# Wattuino-Nanite85_v10.net
KiCad netlist of a schematic drawn in EAGLE
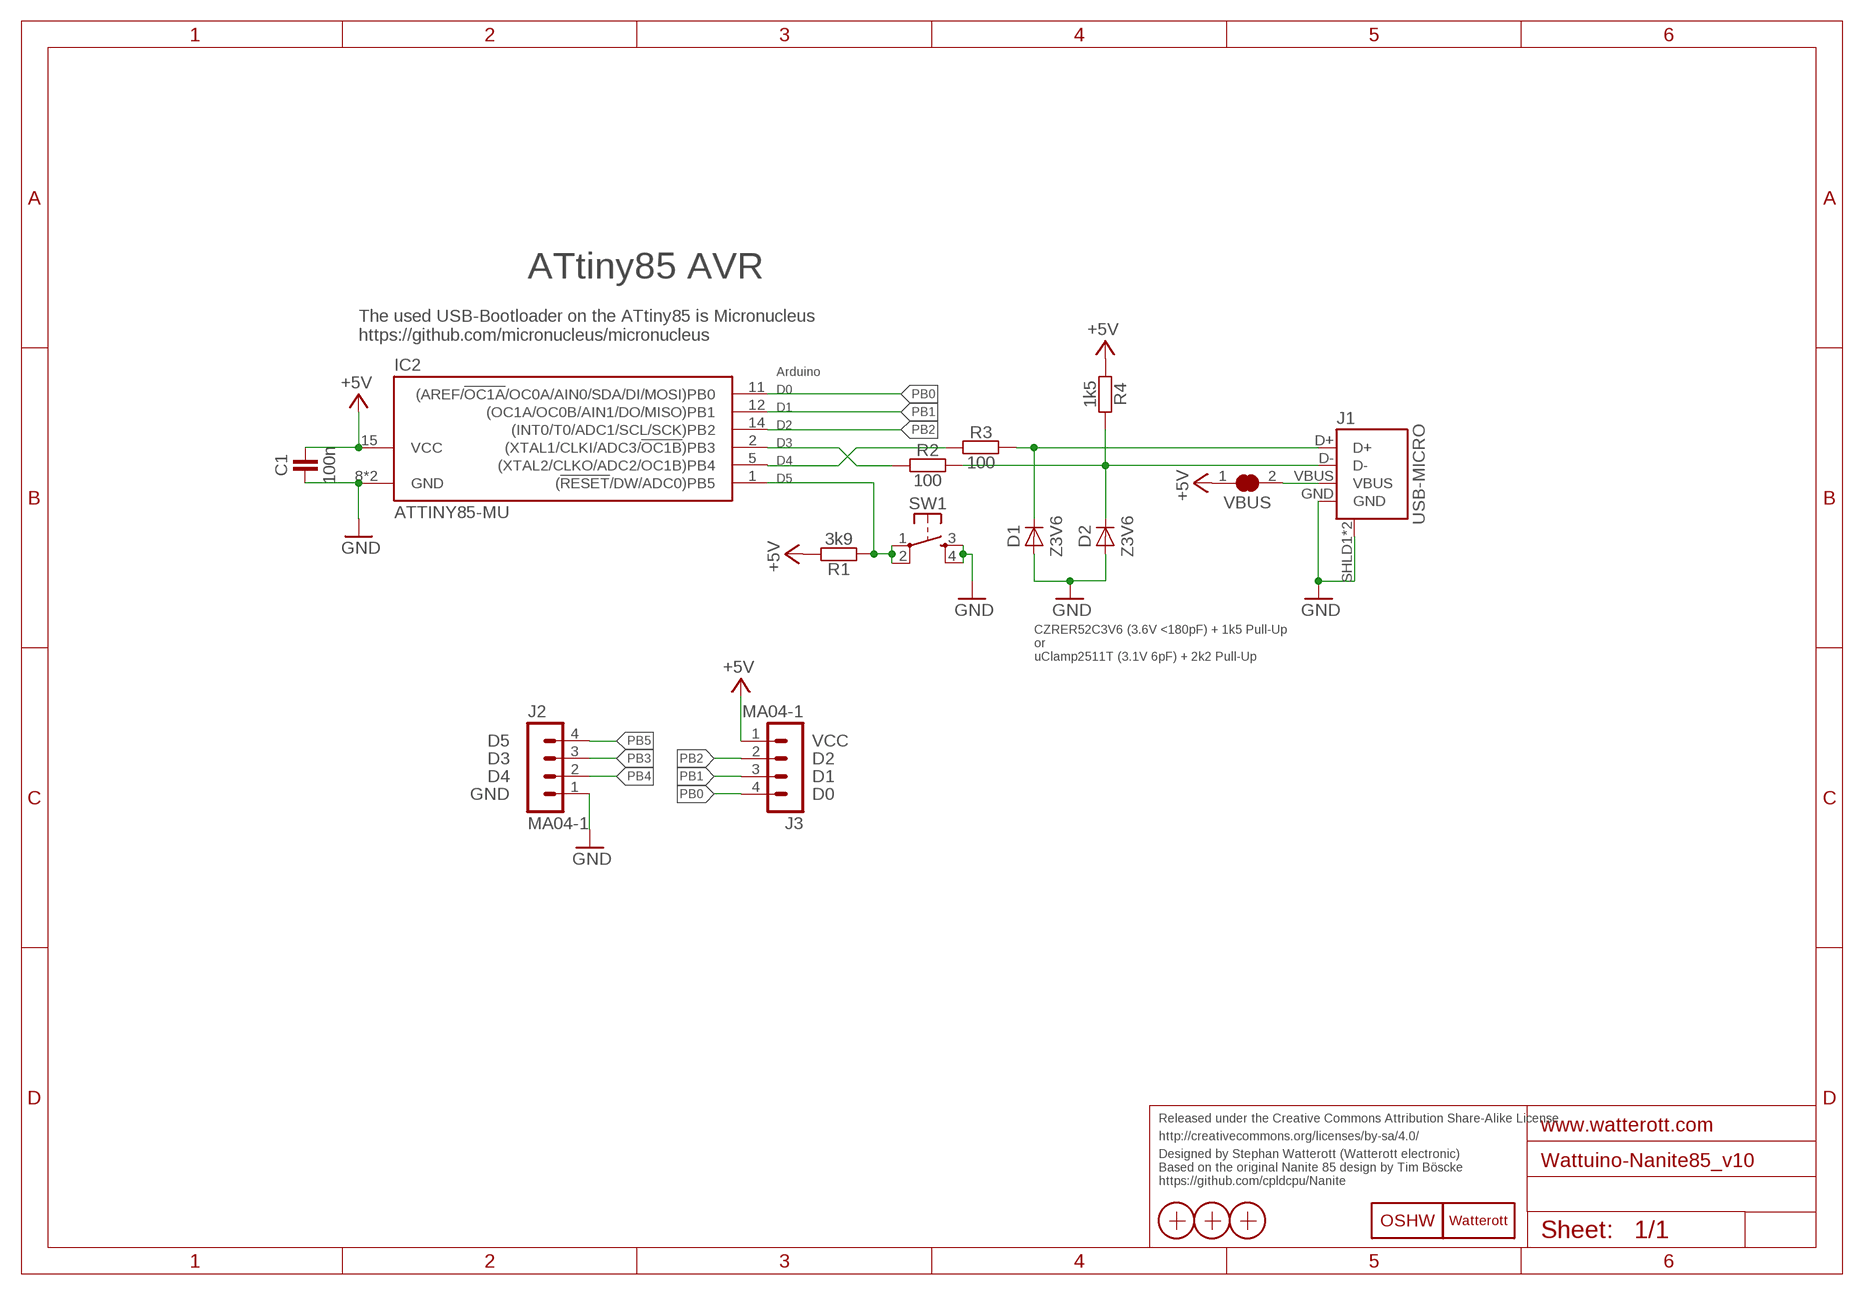
[diagram p0: schematic, sheet 1]

(export (version "E")
  (design (tool "Eeschema 10.0.6"))
  (components
    (comp (ref "C1")
      (value "100n")
      (footprint "eagle-import:C0402")
      (libsource (lib "eagle-import") (part "CAPACITOR-0402"))
    )
    (comp (ref "D1")
      (value "Z3V6")
      (footprint "eagle-import:SOD882")
      (libsource (lib "eagle-import") (part "DIODE-SOD882"))
    )
    (comp (ref "D2")
      (value "Z3V6")
      (footprint "eagle-import:SOD882")
      (libsource (lib "eagle-import") (part "DIODE-SOD882"))
    )
    (comp (ref "IC2")
      (value "ATTINY85-MU")
      (footprint "eagle-import:QFN20-PAD")
      (libsource (lib "eagle-import") (part "ATTINY85-MU"))
    )
    (comp (ref "J1")
      (value "USB-MICRO")
      (footprint "eagle-import:USB-MICRO-10103594")
      (libsource (lib "eagle-import") (part "USB-MICRO"))
    )
    (comp (ref "J2")
      (value "MA04-1")
      (footprint "eagle-import:MA04-1")
      (libsource (lib "eagle-import") (part "MA04-1"))
    )
    (comp (ref "J3")
      (value "MA04-1")
      (footprint "eagle-import:MA04-1")
      (libsource (lib "eagle-import") (part "MA04-1"))
    )
    (comp (ref "LOGO1")
      (value "LOGO-S_PLACE_S")
      (footprint "eagle-import:SPARK_TPLACE_S")
      (libsource (lib "eagle-import") (part "LOGO-S_PLACE_S"))
    )
    (comp (ref "LOGO2")
      (value "OSHW_LOGOX0070")
      (footprint "eagle-import:OSHW_6X70")
      (libsource (lib "eagle-import") (part "OSHW_LOGOX0070"))
    )
    (comp (ref "R1")
      (value "3k9")
      (footprint "eagle-import:C0402")
      (libsource (lib "eagle-import") (part "RESISTOR-0402"))
    )
    (comp (ref "R2")
      (value "100")
      (footprint "eagle-import:C0402")
      (libsource (lib "eagle-import") (part "RESISTOR-0402"))
    )
    (comp (ref "R3")
      (value "100")
      (footprint "eagle-import:C0402")
      (libsource (lib "eagle-import") (part "RESISTOR-0402"))
    )
    (comp (ref "R4")
      (value "1k5")
      (footprint "eagle-import:C0402")
      (libsource (lib "eagle-import") (part "RESISTOR-0402"))
    )
    (comp (ref "SW1")
      (value "SW-TACTILE-PTS840P")
      (footprint "eagle-import:SW_PTS840P")
      (libsource (lib "eagle-import") (part "SW-TACTILE-PTS840P"))
    )
    (comp (ref "VBUS")
      (value "JUMPER2-0603-NC")
      (footprint "eagle-import:JUMPER2-0603_NC")
      (libsource (lib "eagle-import") (part "JUMPER2-0603-NC"))
    )
    (comp (ref "X1")
      (value "PASSER-07")
      (footprint "eagle-import:PASSER_07MM")
      (libsource (lib "eagle-import") (part "PASSER-07"))
    )
    (comp (ref "X2")
      (value "PASSER-07")
      (footprint "eagle-import:PASSER_07MM")
      (libsource (lib "eagle-import") (part "PASSER-07"))
    )
    (comp (ref "X3")
      (value "PASSER-07")
      (footprint "eagle-import:PASSER_07MM")
      (libsource (lib "eagle-import") (part "PASSER-07"))
    )
  )
  (nets
    (net (code "1") (name "+5V") (class "Default")
      (node (ref "C1") (pin "2") (pinfunction "2_2") (pintype "passive"))
      (node (ref "IC2") (pin "15") (pinfunction "VCC_15") (pintype "power_in"))
      (node (ref "J3") (pin "1") (pinfunction "1_1") (pintype "passive"))
      (node (ref "R1") (pin "2") (pinfunction "2_2") (pintype "passive"))
      (node (ref "R4") (pin "1") (pinfunction "1_1") (pintype "passive"))
      (node (ref "VBUS") (pin "1") (pinfunction "1_1") (pintype "passive"))
    )
    (net (code "2") (name "GND") (class "Default")
      (node (ref "C1") (pin "1") (pinfunction "1_1") (pintype "passive"))
      (node (ref "D1") (pin "A") (pinfunction "A_A") (pintype "passive"))
      (node (ref "D2") (pin "A") (pinfunction "A_A") (pintype "passive"))
      (node (ref "IC2") (pin "8") (pinfunction "GND_8") (pintype "power_in"))
      (node (ref "IC2") (pin "TP") (pinfunction "GND_TP") (pintype "power_in"))
      (node (ref "J1") (pin "GND") (pinfunction "GND_GND") (pintype "power_in"))
      (node (ref "J1") (pin "SHLD1") (pinfunction "SHIELD_SHLD1") (pintype "passive"))
      (node (ref "J1") (pin "SHLD2") (pinfunction "SHIELD_SHLD2") (pintype "passive"))
      (node (ref "J2") (pin "1") (pinfunction "1_1") (pintype "passive"))
      (node (ref "SW1") (pin "3") (pinfunction "S1_3") (pintype "passive"))
      (node (ref "SW1") (pin "4") (pinfunction "S2_4") (pintype "passive"))
    )
    (net (code "3") (name "Net-(D1-PadC)") (class "Default")
      (node (ref "D1") (pin "C") (pinfunction "C_C") (pintype "passive"))
      (node (ref "J1") (pin "D+") (pinfunction "D+_D+") (pintype "bidirectional"))
      (node (ref "R3") (pin "2") (pinfunction "2_2") (pintype "passive"))
    )
    (net (code "4") (name "Net-(D2-PadC)") (class "Default")
      (node (ref "D2") (pin "C") (pinfunction "C_C") (pintype "passive"))
      (node (ref "J1") (pin "D-") (pinfunction "D-_D-") (pintype "bidirectional"))
      (node (ref "R2") (pin "2") (pinfunction "2_2") (pintype "passive"))
      (node (ref "R4") (pin "2") (pinfunction "2_2") (pintype "passive"))
    )
    (net (code "5") (name "Net-(J1-PadVBUS)") (class "Default")
      (node (ref "J1") (pin "VBUS") (pinfunction "VBUS_VBUS") (pintype "power_in"))
      (node (ref "VBUS") (pin "2") (pinfunction "2_2") (pintype "passive"))
    )
    (net (code "6") (name "PB0") (class "Default")
      (node (ref "IC2") (pin "11") (pinfunction "(AREF/~{OC1A}/OC0A/AIN0/SDA/DI/MOSI)PB0_11") (pintype "bidirectional"))
      (node (ref "J3") (pin "4") (pinfunction "4_4") (pintype "passive"))
    )
    (net (code "7") (name "PB1") (class "Default")
      (node (ref "IC2") (pin "12") (pinfunction "(OC1A/OC0B/AIN1/DO/MISO)PB1_12") (pintype "bidirectional"))
      (node (ref "J3") (pin "3") (pinfunction "3_3") (pintype "passive"))
    )
    (net (code "8") (name "PB2") (class "Default")
      (node (ref "IC2") (pin "14") (pinfunction "(INT0/T0/ADC1/SCL/SCK)PB2_14") (pintype "bidirectional"))
      (node (ref "J3") (pin "2") (pinfunction "2_2") (pintype "passive"))
    )
    (net (code "9") (name "PB3") (class "Default")
      (node (ref "IC2") (pin "2") (pinfunction "(XTAL1/CLKI/ADC3/~{OC1B})PB3_2") (pintype "bidirectional"))
      (node (ref "J2") (pin "3") (pinfunction "3_3") (pintype "passive"))
      (node (ref "R2") (pin "1") (pinfunction "1_1") (pintype "passive"))
    )
    (net (code "10") (name "PB4") (class "Default")
      (node (ref "IC2") (pin "5") (pinfunction "(XTAL2/CLKO/ADC2/OC1B)PB4_5") (pintype "bidirectional"))
      (node (ref "J2") (pin "2") (pinfunction "2_2") (pintype "passive"))
      (node (ref "R3") (pin "1") (pinfunction "1_1") (pintype "passive"))
    )
    (net (code "11") (name "PB5") (class "Default")
      (node (ref "IC2") (pin "1") (pinfunction "(~{RESET}/DW/ADC0)PB5_1") (pintype "bidirectional"))
      (node (ref "J2") (pin "4") (pinfunction "4_4") (pintype "passive"))
      (node (ref "R1") (pin "1") (pinfunction "1_1") (pintype "passive"))
      (node (ref "SW1") (pin "1") (pinfunction "P1_1") (pintype "passive"))
      (node (ref "SW1") (pin "2") (pinfunction "P2_2") (pintype "passive"))
    )
  )
)
